# Parallel_Data_Interface.net
KiCad netlist of a schematic drawn in Altium Designer
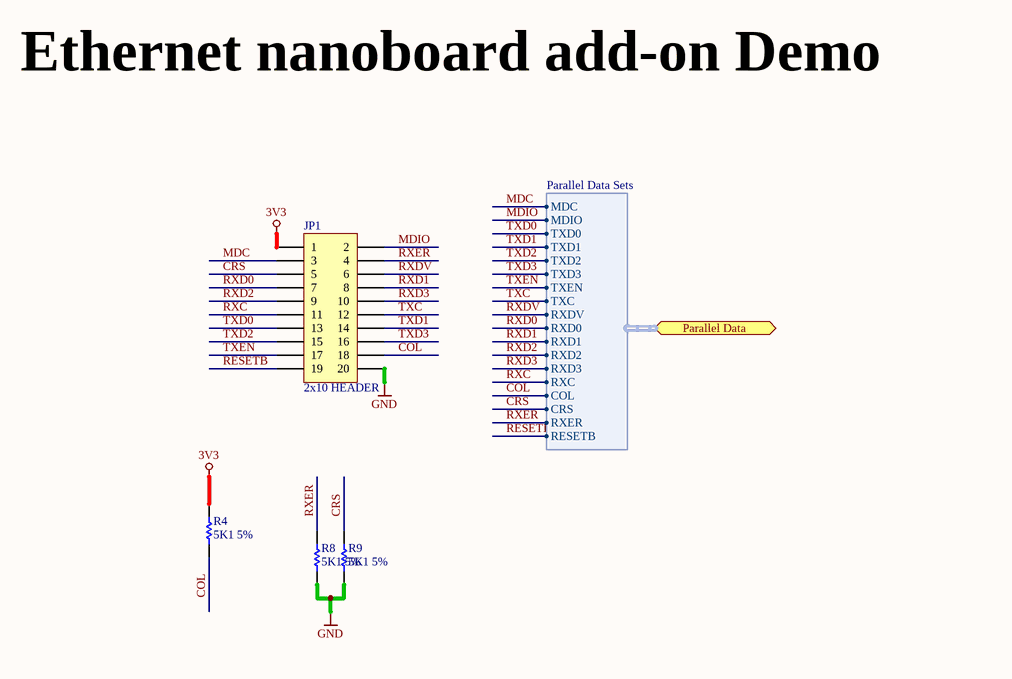
[diagram p0: Parallel Data Interface.SchDoc]

(export (version "E")
  (design (tool "Eeschema 10.0.6"))
  (components
    (comp (ref "JP1")
      (value "2x10 HEADER")
      (footprint "HDR2X10")
      (description "Header, 10-Pin, Dual row")
      (libsource (lib "PHY") (part "CON-HDR-2x10-STR"))
    )
    (comp (ref "R4")
      (value "5K1 5%")
      (footprint "RESC2012")
      (description "Resistor")
      (libsource (lib "PHY") (part "RES"))
    )
    (comp (ref "R8")
      (value "5K1 5%")
      (footprint "RESC2012")
      (description "Resistor")
      (libsource (lib "PHY") (part "RES"))
    )
    (comp (ref "R9")
      (value "5K1 5%")
      (footprint "RESC2012")
      (description "Resistor")
      (libsource (lib "PHY") (part "RES"))
    )
  )
  (nets
    (net (code "4") (name "/COL") (class "Default")
      (node (ref "JP1") (pin "18") (pinfunction "18_18") (pintype "passive"))
      (node (ref "R4") (pin "1") (pinfunction "1_1") (pintype "passive"))
    )
    (net (code "5") (name "/CRS") (class "Default")
      (node (ref "JP1") (pin "5") (pinfunction "5_5") (pintype "passive"))
      (node (ref "R9") (pin "2") (pinfunction "2_2") (pintype "passive"))
    )
    (net (code "6") (name "/MDC") (class "Default")
      (node (ref "JP1") (pin "3") (pinfunction "3_3") (pintype "passive"))
    )
    (net (code "7") (name "/MDIO") (class "Default")
      (node (ref "JP1") (pin "2") (pinfunction "2_2") (pintype "passive"))
    )
    (net (code "8") (name "/RESETB") (class "Default")
      (node (ref "JP1") (pin "19") (pinfunction "19_19") (pintype "passive"))
    )
    (net (code "9") (name "/RXC") (class "Default")
      (node (ref "JP1") (pin "11") (pinfunction "11_11") (pintype "passive"))
    )
    (net (code "10") (name "/RXD0") (class "Default")
      (node (ref "JP1") (pin "7") (pinfunction "7_7") (pintype "passive"))
    )
    (net (code "11") (name "/RXD1") (class "Default")
      (node (ref "JP1") (pin "8") (pinfunction "8_8") (pintype "passive"))
    )
    (net (code "12") (name "/RXD2") (class "Default")
      (node (ref "JP1") (pin "9") (pinfunction "9_9") (pintype "passive"))
    )
    (net (code "13") (name "/RXD3") (class "Default")
      (node (ref "JP1") (pin "10") (pinfunction "10_10") (pintype "passive"))
    )
    (net (code "14") (name "/RXDV") (class "Default")
      (node (ref "JP1") (pin "6") (pinfunction "6_6") (pintype "passive"))
    )
    (net (code "15") (name "/RXER") (class "Default")
      (node (ref "JP1") (pin "4") (pinfunction "4_4") (pintype "passive"))
      (node (ref "R8") (pin "2") (pinfunction "2_2") (pintype "passive"))
    )
    (net (code "16") (name "/TXC") (class "Default")
      (node (ref "JP1") (pin "12") (pinfunction "12_12") (pintype "passive"))
    )
    (net (code "17") (name "/TXD0") (class "Default")
      (node (ref "JP1") (pin "13") (pinfunction "13_13") (pintype "passive"))
    )
    (net (code "18") (name "/TXD1") (class "Default")
      (node (ref "JP1") (pin "14") (pinfunction "14_14") (pintype "passive"))
    )
    (net (code "19") (name "/TXD2") (class "Default")
      (node (ref "JP1") (pin "15") (pinfunction "15_15") (pintype "passive"))
    )
    (net (code "20") (name "/TXD3") (class "Default")
      (node (ref "JP1") (pin "16") (pinfunction "16_16") (pintype "passive"))
    )
    (net (code "21") (name "/TXEN") (class "Default")
      (node (ref "JP1") (pin "17") (pinfunction "17_17") (pintype "passive"))
    )
    (net (code "23") (name "3V3") (class "Default")
      (node (ref "JP1") (pin "1") (pinfunction "1_1") (pintype "passive"))
      (node (ref "R4") (pin "2") (pinfunction "2_2") (pintype "passive"))
    )
    (net (code "24") (name "GND") (class "Default")
      (node (ref "JP1") (pin "20") (pinfunction "20_20") (pintype "passive"))
      (node (ref "R8") (pin "1") (pinfunction "1_1") (pintype "passive"))
      (node (ref "R9") (pin "1") (pinfunction "1_1") (pintype "passive"))
    )
  )
)
